# TimerModule.net
KiCad netlist of a schematic drawn in EAGLE
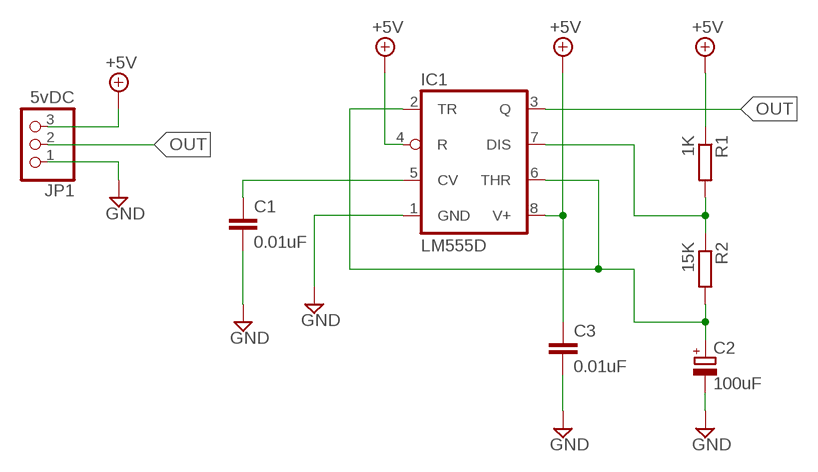
[diagram p0: schematic, sheet 1]

(export (version "E")
  (design (tool "Eeschema 10.0.6"))
  (components
    (comp (ref "C1")
      (value "0.01uF")
      (footprint "eagle-import:C0805")
      (libsource (lib "eagle-import") (part "C-EUC0805"))
    )
    (comp (ref "C2")
      (value "100uF")
      (footprint "eagle-import:E2,5-5")
      (libsource (lib "eagle-import") (part "CPOL-EUE2.5-5"))
    )
    (comp (ref "C3")
      (value "0.01uF")
      (footprint "eagle-import:C0805")
      (libsource (lib "eagle-import") (part "C-EUC0805"))
    )
    (comp (ref "IC1")
      (value "LM555D")
      (footprint "eagle-import:SO08")
      (libsource (lib "eagle-import") (part "555DLM"))
    )
    (comp (ref "JP1")
      (value "5vDC")
      (footprint "eagle-import:1X03")
      (libsource (lib "eagle-import") (part "PINHD-1X3"))
    )
    (comp (ref "R1")
      (value "1K")
      (footprint "eagle-import:M0805")
      (libsource (lib "eagle-import") (part "R-EU_M0805"))
    )
    (comp (ref "R2")
      (value "15K")
      (footprint "eagle-import:M0805")
      (libsource (lib "eagle-import") (part "R-EU_M0805"))
    )
  )
  (nets
    (net (code "1") (name "+5V") (class "Default")
      (node (ref "C3") (pin "1") (pinfunction "1_1") (pintype "passive"))
      (node (ref "IC1") (pin "4") (pinfunction "R_4") (pintype "input"))
      (node (ref "IC1") (pin "8") (pinfunction "V+_8") (pintype "power_in"))
      (node (ref "JP1") (pin "3") (pinfunction "3_3") (pintype "passive"))
      (node (ref "R1") (pin "1") (pinfunction "1_1") (pintype "passive"))
    )
    (net (code "2") (name "GND") (class "Default")
      (node (ref "C1") (pin "2") (pinfunction "2_2") (pintype "passive"))
      (node (ref "C2") (pin "-") (pinfunction "-_-") (pintype "passive"))
      (node (ref "C3") (pin "2") (pinfunction "2_2") (pintype "passive"))
      (node (ref "IC1") (pin "1") (pinfunction "GND_1") (pintype "power_in"))
      (node (ref "JP1") (pin "1") (pinfunction "1_1") (pintype "passive"))
    )
    (net (code "3") (name "Net-(IC1-CV)") (class "Default")
      (node (ref "C1") (pin "1") (pinfunction "1_1") (pintype "passive"))
      (node (ref "IC1") (pin "5") (pinfunction "CV_5") (pintype "input"))
    )
    (net (code "4") (name "Net-(IC1-DIS)") (class "Default")
      (node (ref "IC1") (pin "7") (pinfunction "DIS_7") (pintype "input"))
      (node (ref "R1") (pin "2") (pinfunction "2_2") (pintype "passive"))
      (node (ref "R2") (pin "1") (pinfunction "1_1") (pintype "passive"))
    )
    (net (code "5") (name "Net-(IC1-THR)") (class "Default")
      (node (ref "C2") (pin "+") (pinfunction "+_+") (pintype "passive"))
      (node (ref "IC1") (pin "2") (pinfunction "TR_2") (pintype "input"))
      (node (ref "IC1") (pin "6") (pinfunction "THR_6") (pintype "input"))
      (node (ref "R2") (pin "2") (pinfunction "2_2") (pintype "passive"))
    )
    (net (code "6") (name "OUT") (class "Default")
      (node (ref "IC1") (pin "3") (pinfunction "Q_3") (pintype "output"))
      (node (ref "JP1") (pin "2") (pinfunction "2_2") (pintype "passive"))
    )
  )
)
